# LedEsp32.net
KiCad netlist of a schematic drawn in EAGLE
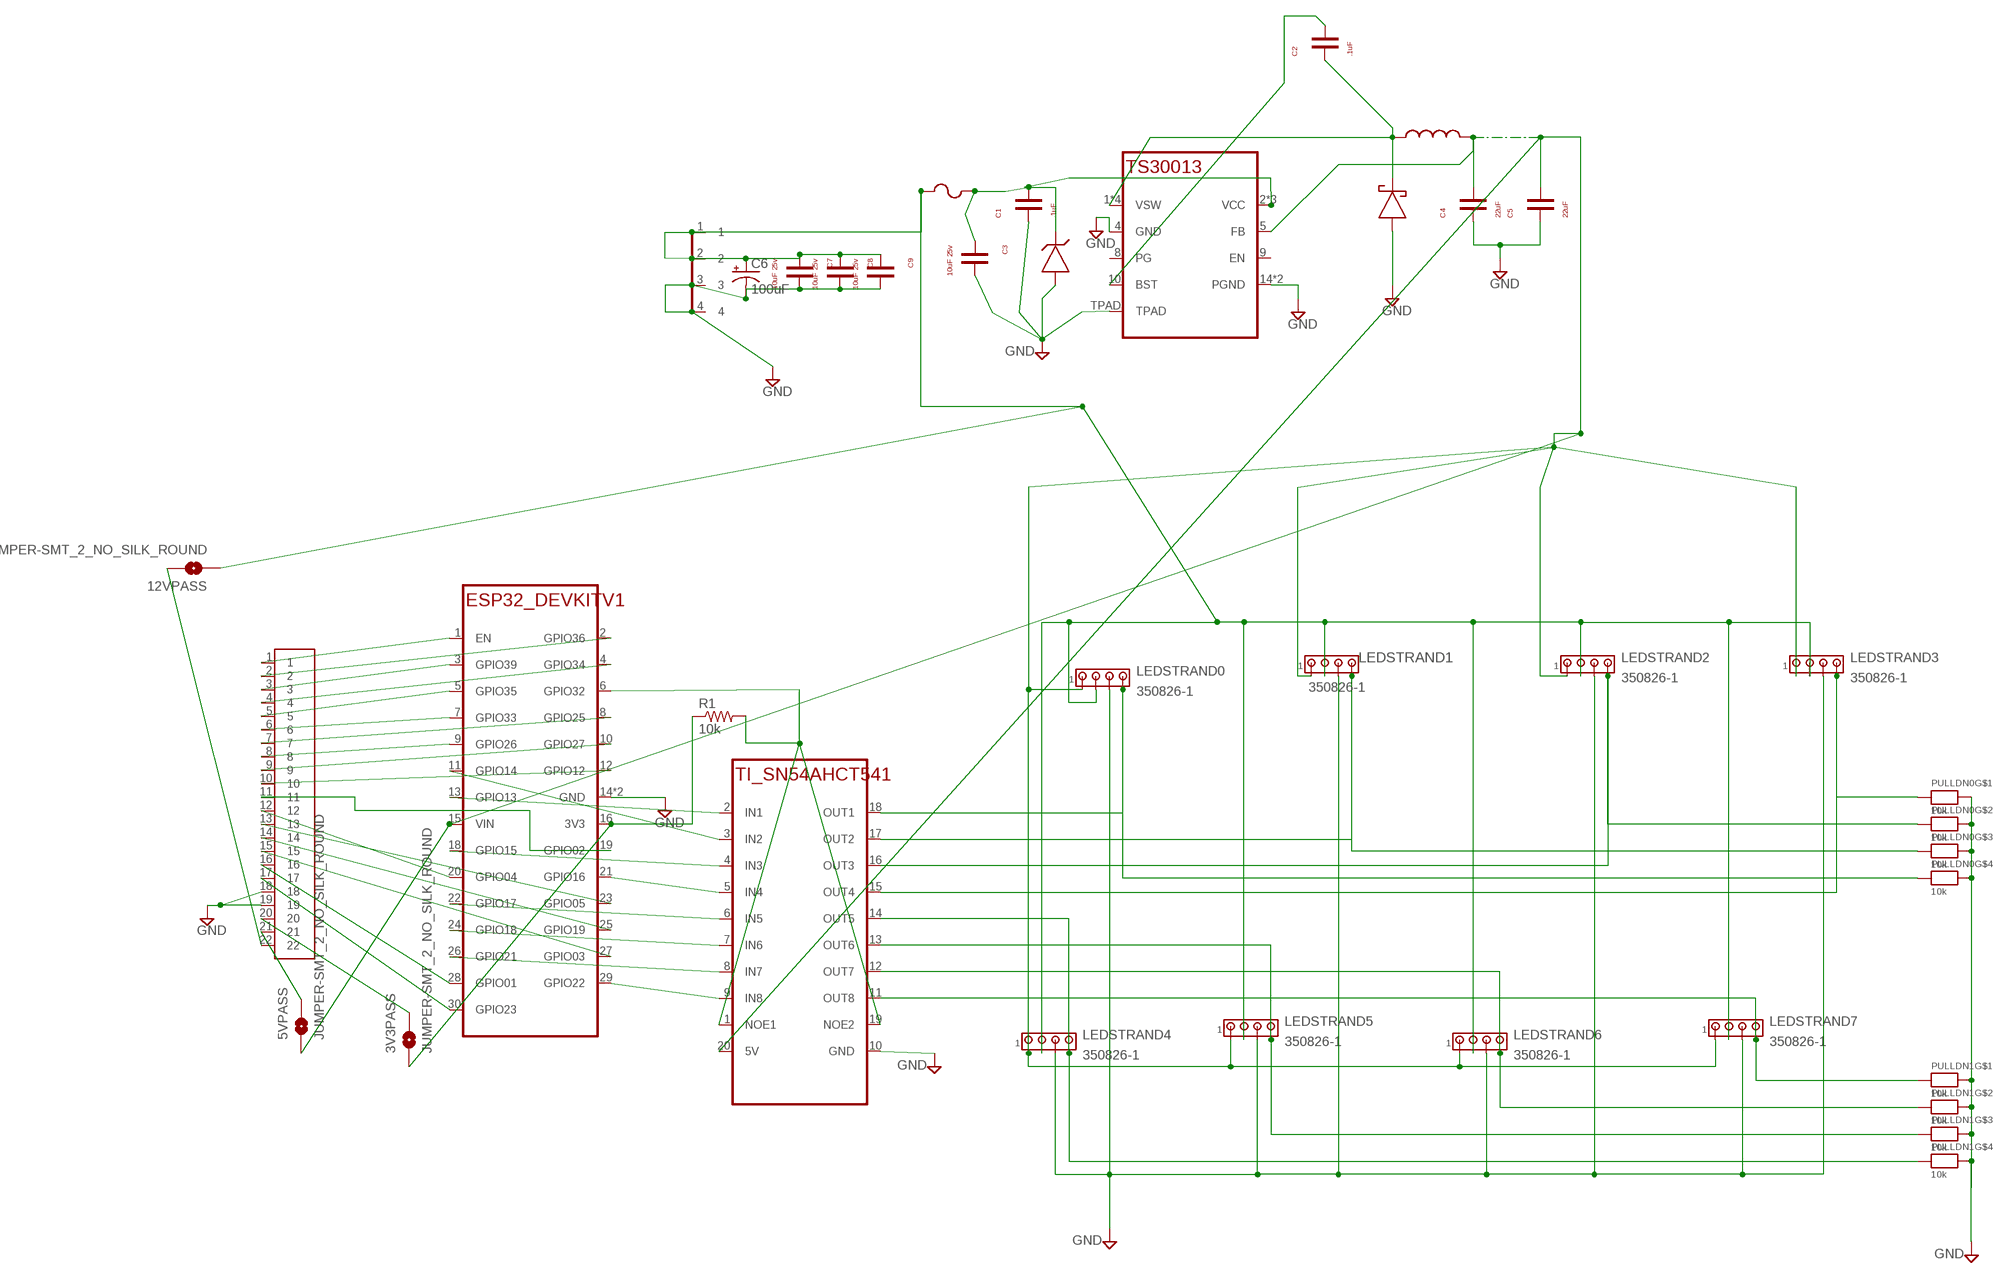
[diagram p0: schematic, sheet 1]

(export (version "E")
  (design (tool "Eeschema 10.0.6"))
  (components
    (comp (ref "3V3PASS")
      (value "JUMPER-SMT_2_NO_SILK_ROUND")
      (footprint "eagle-import:SMT-JUMPER_2_NO_SILK_ROUND")
      (libsource (lib "eagle-import") (part "JUMPER-SMT_2_NO_SILK_ROUND"))
    )
    (comp (ref "5VPASS")
      (value "JUMPER-SMT_2_NO_SILK_ROUND")
      (footprint "eagle-import:SMT-JUMPER_2_NO_SILK_ROUND")
      (libsource (lib "eagle-import") (part "JUMPER-SMT_2_NO_SILK_ROUND"))
    )
    (comp (ref "12VPASS")
      (value "JUMPER-SMT_2_NO_SILK_ROUND")
      (footprint "eagle-import:SMT-JUMPER_2_NO_SILK_ROUND")
      (libsource (lib "eagle-import") (part "JUMPER-SMT_2_NO_SILK_ROUND"))
    )
    (comp (ref "C1")
      (value ".1uF")
      (footprint "eagle-import:C0603")
      (libsource (lib "eagle-import") (part "CAPACITOR_NONPOLARC0603"))
    )
    (comp (ref "C2")
      (value ".1uF")
      (footprint "eagle-import:C0603")
      (libsource (lib "eagle-import") (part "CAPACITOR_NONPOLARC0603"))
    )
    (comp (ref "C3")
      (value "10uF 25v")
      (footprint "eagle-import:C1206")
      (libsource (lib "eagle-import") (part "CL31A106MAHNNNEC1206"))
    )
    (comp (ref "C4")
      (value "22uF")
      (footprint "eagle-import:C0603")
      (libsource (lib "eagle-import") (part "GRM188R61A226ME15DC0603"))
    )
    (comp (ref "C5")
      (value "22uF")
      (footprint "eagle-import:C0603")
      (libsource (lib "eagle-import") (part "GRM188R61A226ME15DC0603"))
    )
    (comp (ref "C6")
      (value "100uF")
      (footprint "eagle-import:E2,5-6")
      (libsource (lib "eagle-import") (part "CPOL-USE2.5-6"))
    )
    (comp (ref "C7")
      (value "10uF 25v")
      (footprint "eagle-import:C1206")
      (libsource (lib "eagle-import") (part "CL31A106MAHNNNEC1206"))
    )
    (comp (ref "C8")
      (value "10uF 25v")
      (footprint "eagle-import:C1206")
      (libsource (lib "eagle-import") (part "CL31A106MAHNNNEC1206"))
    )
    (comp (ref "C9")
      (value "10uF 25v")
      (footprint "eagle-import:C1206")
      (libsource (lib "eagle-import") (part "CL31A106MAHNNNEC1206"))
    )
    (comp (ref "D2")
      (value "LS54LS54")
      (footprint "eagle-import:LS54")
      (libsource (lib "eagle-import") (part "LS54LS54"))
    )
    (comp (ref "F1")
      (value "3A")
      (footprint "eagle-import:R0603")
      (libsource (lib "eagle-import") (part "FUSER0603"))
    )
    (comp (ref "IC1")
      (value "TS30013QFN16")
      (footprint "eagle-import:QFN16")
      (libsource (lib "eagle-import") (part "TS30013QFN16"))
    )
    (comp (ref "L1")
      (value "SRN5040TA-4R7MSRN5040TA")
      (footprint "eagle-import:SRN5040TA")
      (libsource (lib "eagle-import") (part "SRN5040TA-4R7MSRN5040TA"))
    )
    (comp (ref "LEDSTRAND0")
      (value "350826-1")
      (footprint "eagle-import:350826-1")
      (libsource (lib "eagle-import") (part "350826-1"))
    )
    (comp (ref "LEDSTRAND1")
      (value "350826-1")
      (footprint "eagle-import:350826-1")
      (libsource (lib "eagle-import") (part "350826-1"))
    )
    (comp (ref "LEDSTRAND2")
      (value "350826-1")
      (footprint "eagle-import:350826-1")
      (libsource (lib "eagle-import") (part "350826-1"))
    )
    (comp (ref "LEDSTRAND3")
      (value "350826-1")
      (footprint "eagle-import:350826-1")
      (libsource (lib "eagle-import") (part "350826-1"))
    )
    (comp (ref "LEDSTRAND4")
      (value "350826-1")
      (footprint "eagle-import:350826-1")
      (libsource (lib "eagle-import") (part "350826-1"))
    )
    (comp (ref "LEDSTRAND5")
      (value "350826-1")
      (footprint "eagle-import:350826-1")
      (libsource (lib "eagle-import") (part "350826-1"))
    )
    (comp (ref "LEDSTRAND6")
      (value "350826-1")
      (footprint "eagle-import:350826-1")
      (libsource (lib "eagle-import") (part "350826-1"))
    )
    (comp (ref "LEDSTRAND7")
      (value "350826-1")
      (footprint "eagle-import:350826-1")
      (libsource (lib "eagle-import") (part "350826-1"))
    )
    (comp (ref "PULLDN0")
      (value "10k")
      (footprint "eagle-import:RESPACK_4X0603")
      (libsource (lib "eagle-import") (part "RESISTOR_4PACK"))
    )
    (comp (ref "PULLDN1")
      (value "10k")
      (footprint "eagle-import:RESPACK_4X0603")
      (libsource (lib "eagle-import") (part "RESISTOR_4PACK"))
    )
    (comp (ref "R1")
      (value "10k")
      (footprint "eagle-import:R0603")
      (libsource (lib "eagle-import") (part "R-US_R0603"))
    )
    (comp (ref "U$1")
      (value "ESP32_DEVKITV1ESP32_DEVKITV1DEVINST")
      (footprint "eagle-import:ESP32_DEVKITV1")
      (libsource (lib "eagle-import") (part "ESP32_DEVKITV1ESP32_DEVKITV1DEVINST"))
    )
    (comp (ref "U$2")
      (value "TI_SN54AHCT541SO20WDEVINST")
      (footprint "eagle-import:SO20W")
      (libsource (lib "eagle-import") (part "TI_SN54AHCT541SO20WDEVINST"))
    )
    (comp (ref "U$3")
      (value "1X22THM")
      (footprint "eagle-import:1X22")
      (libsource (lib "eagle-import") (part "1X22THM"))
    )
    (comp (ref "U$4")
      (value "TE-1969806-1TE-1969806-1DEVINST")
      (footprint "eagle-import:TE-1969806-1")
      (libsource (lib "eagle-import") (part "TE-1969806-1TE-1969806-1DEVINST"))
    )
    (comp (ref "Z1")
      (value "CZRB5353B-HF DO-214AADEVINST")
      (footprint "eagle-import:DO-214AA")
      (libsource (lib "eagle-import") (part "CZRB5353B-HF‎DO-214AADEVINST"))
    )
  )
  (nets
    (net (code "1") (name "GND") (class "Default")
      (node (ref "C1") (pin "1") (pinfunction "1_1") (pintype "bidirectional"))
      (node (ref "C3") (pin "2") (pinfunction "2_2") (pintype "bidirectional"))
      (node (ref "C4") (pin "1") (pinfunction "1_1") (pintype "bidirectional"))
      (node (ref "C5") (pin "1") (pinfunction "1_1") (pintype "bidirectional"))
      (node (ref "C6") (pin "-") (pinfunction "-_-") (pintype "passive"))
      (node (ref "C7") (pin "2") (pinfunction "2_2") (pintype "bidirectional"))
      (node (ref "C8") (pin "2") (pinfunction "2_2") (pintype "bidirectional"))
      (node (ref "C9") (pin "2") (pinfunction "2_2") (pintype "bidirectional"))
      (node (ref "D2") (pin "1") (pinfunction "1_1") (pintype "bidirectional"))
      (node (ref "IC1") (pin "14") (pinfunction "PGND_14") (pintype "bidirectional"))
      (node (ref "IC1") (pin "15") (pinfunction "PGND_15") (pintype "bidirectional"))
      (node (ref "IC1") (pin "4") (pinfunction "GND_4") (pintype "bidirectional"))
      (node (ref "IC1") (pin "TPAD") (pinfunction "TPAD_TPAD") (pintype "bidirectional"))
      (node (ref "LEDSTRAND0") (pin "3") (pinfunction "3_3") (pintype "passive"))
      (node (ref "LEDSTRAND1") (pin "3") (pinfunction "3_3") (pintype "passive"))
      (node (ref "LEDSTRAND2") (pin "3") (pinfunction "3_3") (pintype "passive"))
      (node (ref "LEDSTRAND3") (pin "3") (pinfunction "3_3") (pintype "passive"))
      (node (ref "LEDSTRAND4") (pin "3") (pinfunction "3_3") (pintype "passive"))
      (node (ref "LEDSTRAND5") (pin "3") (pinfunction "3_3") (pintype "passive"))
      (node (ref "LEDSTRAND6") (pin "3") (pinfunction "3_3") (pintype "passive"))
      (node (ref "LEDSTRAND7") (pin "3") (pinfunction "3_3") (pintype "passive"))
      (node (ref "PULLDN0") (pin "5") (pinfunction "2_5") (pintype "passive"))
      (node (ref "PULLDN0") (pin "6") (pinfunction "2_6") (pintype "passive"))
      (node (ref "PULLDN0") (pin "7") (pinfunction "2_7") (pintype "passive"))
      (node (ref "PULLDN0") (pin "8") (pinfunction "2_8") (pintype "passive"))
      (node (ref "PULLDN1") (pin "5") (pinfunction "2_5") (pintype "passive"))
      (node (ref "PULLDN1") (pin "6") (pinfunction "2_6") (pintype "passive"))
      (node (ref "PULLDN1") (pin "7") (pinfunction "2_7") (pintype "passive"))
      (node (ref "PULLDN1") (pin "8") (pinfunction "2_8") (pintype "passive"))
      (node (ref "U$1") (pin "14") (pinfunction "GND_14") (pintype "bidirectional"))
      (node (ref "U$1") (pin "17") (pinfunction "GND_17") (pintype "bidirectional"))
      (node (ref "U$2") (pin "10") (pinfunction "GND_10") (pintype "bidirectional"))
      (node (ref "U$3") (pin "18") (pinfunction "18_18") (pintype "bidirectional"))
      (node (ref "U$3") (pin "19") (pinfunction "19_19") (pintype "bidirectional"))
      (node (ref "U$4") (pin "3") (pinfunction "3_3") (pintype "bidirectional"))
      (node (ref "U$4") (pin "4") (pinfunction "4_4") (pintype "bidirectional"))
      (node (ref "Z1") (pin "1") (pinfunction "1_1") (pintype "bidirectional"))
    )
    (net (code "2") (name "Net-(3V3PASS-Pad2)") (class "Default")
      (node (ref "3V3PASS") (pin "2") (pinfunction "2_2") (pintype "passive"))
      (node (ref "U$3") (pin "20") (pinfunction "20_20") (pintype "bidirectional"))
    )
    (net (code "3") (name "Net-(5VPASS-Pad2)") (class "Default")
      (node (ref "5VPASS") (pin "2") (pinfunction "2_2") (pintype "passive"))
      (node (ref "U$3") (pin "21") (pinfunction "21_21") (pintype "bidirectional"))
    )
    (net (code "4") (name "Net-(12VPASS-Pad1)") (class "Default")
      (node (ref "12VPASS") (pin "1") (pinfunction "1_1") (pintype "passive"))
      (node (ref "C6") (pin "+") (pinfunction "+_+") (pintype "passive"))
      (node (ref "C7") (pin "1") (pinfunction "1_1") (pintype "bidirectional"))
      (node (ref "C8") (pin "1") (pinfunction "1_1") (pintype "bidirectional"))
      (node (ref "C9") (pin "1") (pinfunction "1_1") (pintype "bidirectional"))
      (node (ref "F1") (pin "1") (pinfunction "1_1") (pintype "bidirectional"))
      (node (ref "LEDSTRAND0") (pin "2") (pinfunction "2_2") (pintype "passive"))
      (node (ref "LEDSTRAND1") (pin "2") (pinfunction "2_2") (pintype "passive"))
      (node (ref "LEDSTRAND2") (pin "2") (pinfunction "2_2") (pintype "passive"))
      (node (ref "LEDSTRAND3") (pin "2") (pinfunction "2_2") (pintype "passive"))
      (node (ref "LEDSTRAND4") (pin "2") (pinfunction "2_2") (pintype "passive"))
      (node (ref "LEDSTRAND5") (pin "2") (pinfunction "2_2") (pintype "passive"))
      (node (ref "LEDSTRAND6") (pin "2") (pinfunction "2_2") (pintype "passive"))
      (node (ref "LEDSTRAND7") (pin "2") (pinfunction "2_2") (pintype "passive"))
      (node (ref "U$4") (pin "1") (pinfunction "1_1") (pintype "bidirectional"))
      (node (ref "U$4") (pin "2") (pinfunction "2_2") (pintype "bidirectional"))
    )
    (net (code "5") (name "Net-(12VPASS-Pad2)") (class "Default")
      (node (ref "12VPASS") (pin "2") (pinfunction "2_2") (pintype "passive"))
      (node (ref "U$3") (pin "22") (pinfunction "22_22") (pintype "bidirectional"))
    )
    (net (code "6") (name "Net-(C1-Pad2)") (class "Default")
      (node (ref "C1") (pin "2") (pinfunction "2_2") (pintype "bidirectional"))
      (node (ref "C3") (pin "1") (pinfunction "1_1") (pintype "bidirectional"))
      (node (ref "F1") (pin "2") (pinfunction "2_2") (pintype "bidirectional"))
      (node (ref "IC1") (pin "11") (pinfunction "VCC_11") (pintype "bidirectional"))
      (node (ref "IC1") (pin "2") (pinfunction "VCC_2") (pintype "bidirectional"))
      (node (ref "IC1") (pin "3") (pinfunction "VCC_3") (pintype "bidirectional"))
      (node (ref "Z1") (pin "2") (pinfunction "2_2") (pintype "bidirectional"))
    )
    (net (code "7") (name "Net-(C2-Pad1)") (class "Default")
      (node (ref "C2") (pin "1") (pinfunction "1_1") (pintype "bidirectional"))
      (node (ref "D2") (pin "2") (pinfunction "2_2") (pintype "bidirectional"))
      (node (ref "IC1") (pin "1") (pinfunction "VSW_1") (pintype "bidirectional"))
      (node (ref "IC1") (pin "12") (pinfunction "VSW_12") (pintype "bidirectional"))
      (node (ref "IC1") (pin "13") (pinfunction "VSW_13") (pintype "bidirectional"))
      (node (ref "IC1") (pin "16") (pinfunction "VSW_16") (pintype "bidirectional"))
      (node (ref "L1") (pin "1") (pinfunction "1_1") (pintype "bidirectional"))
    )
    (net (code "8") (name "Net-(IC1-BST)") (class "Default")
      (node (ref "C2") (pin "2") (pinfunction "2_2") (pintype "bidirectional"))
      (node (ref "IC1") (pin "10") (pinfunction "BST_10") (pintype "bidirectional"))
    )
    (net (code "9") (name "Net-(IC1-FB)") (class "Default")
      (node (ref "5VPASS") (pin "1") (pinfunction "1_1") (pintype "passive"))
      (node (ref "C4") (pin "2") (pinfunction "2_2") (pintype "bidirectional"))
      (node (ref "C5") (pin "2") (pinfunction "2_2") (pintype "bidirectional"))
      (node (ref "IC1") (pin "5") (pinfunction "FB_5") (pintype "bidirectional"))
      (node (ref "L1") (pin "2") (pinfunction "2_2") (pintype "bidirectional"))
      (node (ref "LEDSTRAND0") (pin "1") (pinfunction "1_1") (pintype "passive"))
      (node (ref "LEDSTRAND1") (pin "1") (pinfunction "1_1") (pintype "passive"))
      (node (ref "LEDSTRAND2") (pin "1") (pinfunction "1_1") (pintype "passive"))
      (node (ref "LEDSTRAND3") (pin "1") (pinfunction "1_1") (pintype "passive"))
      (node (ref "LEDSTRAND4") (pin "1") (pinfunction "1_1") (pintype "passive"))
      (node (ref "LEDSTRAND5") (pin "1") (pinfunction "1_1") (pintype "passive"))
      (node (ref "LEDSTRAND6") (pin "1") (pinfunction "1_1") (pintype "passive"))
      (node (ref "LEDSTRAND7") (pin "1") (pinfunction "1_1") (pintype "passive"))
      (node (ref "U$1") (pin "15") (pinfunction "VIN_15") (pintype "bidirectional"))
      (node (ref "U$2") (pin "20") (pinfunction "5V_20") (pintype "bidirectional"))
    )
    (net (code "10") (name "Net-(PULLDN0B-1)") (class "Default")
      (node (ref "LEDSTRAND2") (pin "4") (pinfunction "4_4") (pintype "passive"))
      (node (ref "PULLDN0") (pin "2") (pinfunction "1_2") (pintype "passive"))
      (node (ref "U$2") (pin "16") (pinfunction "OUT3_16") (pintype "bidirectional"))
    )
    (net (code "11") (name "Net-(PULLDN0C-1)") (class "Default")
      (node (ref "LEDSTRAND1") (pin "4") (pinfunction "4_4") (pintype "passive"))
      (node (ref "PULLDN0") (pin "3") (pinfunction "1_3") (pintype "passive"))
      (node (ref "U$2") (pin "17") (pinfunction "OUT2_17") (pintype "bidirectional"))
    )
    (net (code "12") (name "Net-(PULLDN0D-1)") (class "Default")
      (node (ref "LEDSTRAND0") (pin "4") (pinfunction "4_4") (pintype "passive"))
      (node (ref "PULLDN0") (pin "4") (pinfunction "1_4") (pintype "passive"))
      (node (ref "U$2") (pin "18") (pinfunction "OUT1_18") (pintype "bidirectional"))
    )
    (net (code "13") (name "Net-(PULLDN1B-1)") (class "Default")
      (node (ref "LEDSTRAND6") (pin "4") (pinfunction "4_4") (pintype "passive"))
      (node (ref "PULLDN1") (pin "2") (pinfunction "1_2") (pintype "passive"))
      (node (ref "U$2") (pin "12") (pinfunction "OUT7_12") (pintype "bidirectional"))
    )
    (net (code "14") (name "Net-(PULLDN1C-1)") (class "Default")
      (node (ref "LEDSTRAND5") (pin "4") (pinfunction "4_4") (pintype "passive"))
      (node (ref "PULLDN1") (pin "3") (pinfunction "1_3") (pintype "passive"))
      (node (ref "U$2") (pin "13") (pinfunction "OUT6_13") (pintype "bidirectional"))
    )
    (net (code "15") (name "Net-(PULLDN1D-1)") (class "Default")
      (node (ref "LEDSTRAND4") (pin "4") (pinfunction "4_4") (pintype "passive"))
      (node (ref "PULLDN1") (pin "4") (pinfunction "1_4") (pintype "passive"))
      (node (ref "U$2") (pin "14") (pinfunction "OUT5_14") (pintype "bidirectional"))
    )
    (net (code "16") (name "Net-(U$1-3V3)") (class "Default")
      (node (ref "3V3PASS") (pin "1") (pinfunction "1_1") (pintype "passive"))
      (node (ref "R1") (pin "1") (pinfunction "1_1") (pintype "passive"))
      (node (ref "U$1") (pin "16") (pinfunction "3V3_16") (pintype "bidirectional"))
    )
    (net (code "17") (name "Net-(U$1-EN)") (class "Default")
      (node (ref "U$1") (pin "1") (pinfunction "EN_1") (pintype "bidirectional"))
      (node (ref "U$3") (pin "1") (pinfunction "1_1") (pintype "bidirectional"))
    )
    (net (code "18") (name "Net-(U$1-GPIO01)") (class "Default")
      (node (ref "U$1") (pin "28") (pinfunction "GPIO01_28") (pintype "bidirectional"))
      (node (ref "U$3") (pin "16") (pinfunction "16_16") (pintype "bidirectional"))
    )
    (net (code "19") (name "Net-(U$1-GPIO02)") (class "Default")
      (node (ref "U$1") (pin "19") (pinfunction "GPIO02_19") (pintype "bidirectional"))
      (node (ref "U$3") (pin "11") (pinfunction "11_11") (pintype "bidirectional"))
    )
    (net (code "20") (name "Net-(U$1-GPIO03)") (class "Default")
      (node (ref "U$1") (pin "27") (pinfunction "GPIO03_27") (pintype "bidirectional"))
      (node (ref "U$3") (pin "15") (pinfunction "15_15") (pintype "bidirectional"))
    )
    (net (code "21") (name "Net-(U$1-GPIO04)") (class "Default")
      (node (ref "U$1") (pin "20") (pinfunction "GPIO04_20") (pintype "bidirectional"))
      (node (ref "U$3") (pin "12") (pinfunction "12_12") (pintype "bidirectional"))
    )
    (net (code "22") (name "Net-(U$1-GPIO05)") (class "Default")
      (node (ref "U$1") (pin "23") (pinfunction "GPIO05_23") (pintype "bidirectional"))
      (node (ref "U$3") (pin "13") (pinfunction "13_13") (pintype "bidirectional"))
    )
    (net (code "23") (name "Net-(U$1-GPIO12)") (class "Default")
      (node (ref "U$1") (pin "12") (pinfunction "GPIO12_12") (pintype "bidirectional"))
      (node (ref "U$3") (pin "10") (pinfunction "10_10") (pintype "bidirectional"))
    )
    (net (code "24") (name "Net-(U$1-GPIO13)") (class "Default")
      (node (ref "U$1") (pin "13") (pinfunction "GPIO13_13") (pintype "bidirectional"))
      (node (ref "U$2") (pin "2") (pinfunction "IN1_2") (pintype "bidirectional"))
    )
    (net (code "25") (name "Net-(U$1-GPIO14)") (class "Default")
      (node (ref "U$1") (pin "11") (pinfunction "GPIO14_11") (pintype "bidirectional"))
      (node (ref "U$2") (pin "3") (pinfunction "IN2_3") (pintype "bidirectional"))
    )
    (net (code "26") (name "Net-(U$1-GPIO15)") (class "Default")
      (node (ref "U$1") (pin "18") (pinfunction "GPIO15_18") (pintype "bidirectional"))
      (node (ref "U$2") (pin "4") (pinfunction "IN3_4") (pintype "bidirectional"))
    )
    (net (code "27") (name "Net-(U$1-GPIO16)") (class "Default")
      (node (ref "U$1") (pin "21") (pinfunction "GPIO16_21") (pintype "bidirectional"))
      (node (ref "U$2") (pin "5") (pinfunction "IN4_5") (pintype "bidirectional"))
    )
    (net (code "28") (name "Net-(U$1-GPIO17)") (class "Default")
      (node (ref "U$1") (pin "22") (pinfunction "GPIO17_22") (pintype "bidirectional"))
      (node (ref "U$2") (pin "6") (pinfunction "IN5_6") (pintype "bidirectional"))
    )
    (net (code "29") (name "Net-(U$1-GPIO18)") (class "Default")
      (node (ref "U$1") (pin "24") (pinfunction "GPIO18_24") (pintype "bidirectional"))
      (node (ref "U$2") (pin "7") (pinfunction "IN6_7") (pintype "bidirectional"))
    )
    (net (code "30") (name "Net-(U$1-GPIO19)") (class "Default")
      (node (ref "U$1") (pin "25") (pinfunction "GPIO19_25") (pintype "bidirectional"))
      (node (ref "U$3") (pin "14") (pinfunction "14_14") (pintype "bidirectional"))
    )
    (net (code "31") (name "Net-(U$1-GPIO21)") (class "Default")
      (node (ref "U$1") (pin "26") (pinfunction "GPIO21_26") (pintype "bidirectional"))
      (node (ref "U$2") (pin "8") (pinfunction "IN7_8") (pintype "bidirectional"))
    )
    (net (code "32") (name "Net-(U$1-GPIO22)") (class "Default")
      (node (ref "U$1") (pin "29") (pinfunction "GPIO22_29") (pintype "bidirectional"))
      (node (ref "U$2") (pin "9") (pinfunction "IN8_9") (pintype "bidirectional"))
    )
    (net (code "33") (name "Net-(U$1-GPIO23)") (class "Default")
      (node (ref "U$1") (pin "30") (pinfunction "GPIO23_30") (pintype "bidirectional"))
      (node (ref "U$3") (pin "17") (pinfunction "17_17") (pintype "bidirectional"))
    )
    (net (code "34") (name "Net-(U$1-GPIO25)") (class "Default")
      (node (ref "U$1") (pin "8") (pinfunction "GPIO25_8") (pintype "bidirectional"))
      (node (ref "U$3") (pin "7") (pinfunction "7_7") (pintype "bidirectional"))
    )
    (net (code "35") (name "Net-(U$1-GPIO26)") (class "Default")
      (node (ref "U$1") (pin "9") (pinfunction "GPIO26_9") (pintype "bidirectional"))
      (node (ref "U$3") (pin "8") (pinfunction "8_8") (pintype "bidirectional"))
    )
    (net (code "36") (name "Net-(U$1-GPIO27)") (class "Default")
      (node (ref "U$1") (pin "10") (pinfunction "GPIO27_10") (pintype "bidirectional"))
      (node (ref "U$3") (pin "9") (pinfunction "9_9") (pintype "bidirectional"))
    )
    (net (code "37") (name "Net-(U$1-GPIO32)") (class "Default")
      (node (ref "R1") (pin "2") (pinfunction "2_2") (pintype "passive"))
      (node (ref "U$1") (pin "6") (pinfunction "GPIO32_6") (pintype "bidirectional"))
      (node (ref "U$2") (pin "1") (pinfunction "NOE1_1") (pintype "bidirectional"))
      (node (ref "U$2") (pin "19") (pinfunction "NOE2_19") (pintype "bidirectional"))
    )
    (net (code "38") (name "Net-(U$1-GPIO33)") (class "Default")
      (node (ref "U$1") (pin "7") (pinfunction "GPIO33_7") (pintype "bidirectional"))
      (node (ref "U$3") (pin "6") (pinfunction "6_6") (pintype "bidirectional"))
    )
    (net (code "39") (name "Net-(U$1-GPIO34)") (class "Default")
      (node (ref "U$1") (pin "4") (pinfunction "GPIO34_4") (pintype "bidirectional"))
      (node (ref "U$3") (pin "4") (pinfunction "4_4") (pintype "bidirectional"))
    )
    (net (code "40") (name "Net-(U$1-GPIO35)") (class "Default")
      (node (ref "U$1") (pin "5") (pinfunction "GPIO35_5") (pintype "bidirectional"))
      (node (ref "U$3") (pin "5") (pinfunction "5_5") (pintype "bidirectional"))
    )
    (net (code "41") (name "Net-(U$1-GPIO36)") (class "Default")
      (node (ref "U$1") (pin "2") (pinfunction "GPIO36_2") (pintype "bidirectional"))
      (node (ref "U$3") (pin "2") (pinfunction "2_2") (pintype "bidirectional"))
    )
    (net (code "42") (name "Net-(U$1-GPIO39)") (class "Default")
      (node (ref "U$1") (pin "3") (pinfunction "GPIO39_3") (pintype "bidirectional"))
      (node (ref "U$3") (pin "3") (pinfunction "3_3") (pintype "bidirectional"))
    )
    (net (code "43") (name "Net-(U$2-OUT4)") (class "Default")
      (node (ref "LEDSTRAND3") (pin "4") (pinfunction "4_4") (pintype "passive"))
      (node (ref "PULLDN0") (pin "1") (pinfunction "1_1") (pintype "passive"))
      (node (ref "U$2") (pin "15") (pinfunction "OUT4_15") (pintype "bidirectional"))
    )
    (net (code "44") (name "Net-(U$2-OUT8)") (class "Default")
      (node (ref "LEDSTRAND7") (pin "4") (pinfunction "4_4") (pintype "passive"))
      (node (ref "PULLDN1") (pin "1") (pinfunction "1_1") (pintype "passive"))
      (node (ref "U$2") (pin "11") (pinfunction "OUT8_11") (pintype "bidirectional"))
    )
    (net (code "45") (name "unconnected-(IC1-EN-Pad9)") (class "Default")
      (node (ref "IC1") (pin "9") (pinfunction "EN_9") (pintype "bidirectional"))
    )
    (net (code "46") (name "unconnected-(IC1-PG-Pad8)") (class "Default")
      (node (ref "IC1") (pin "8") (pinfunction "PG_8") (pintype "bidirectional"))
    )
  )
)
